# Untitled_-_halv_V3_31.net
KiCad netlist of a schematic drawn in EAGLE
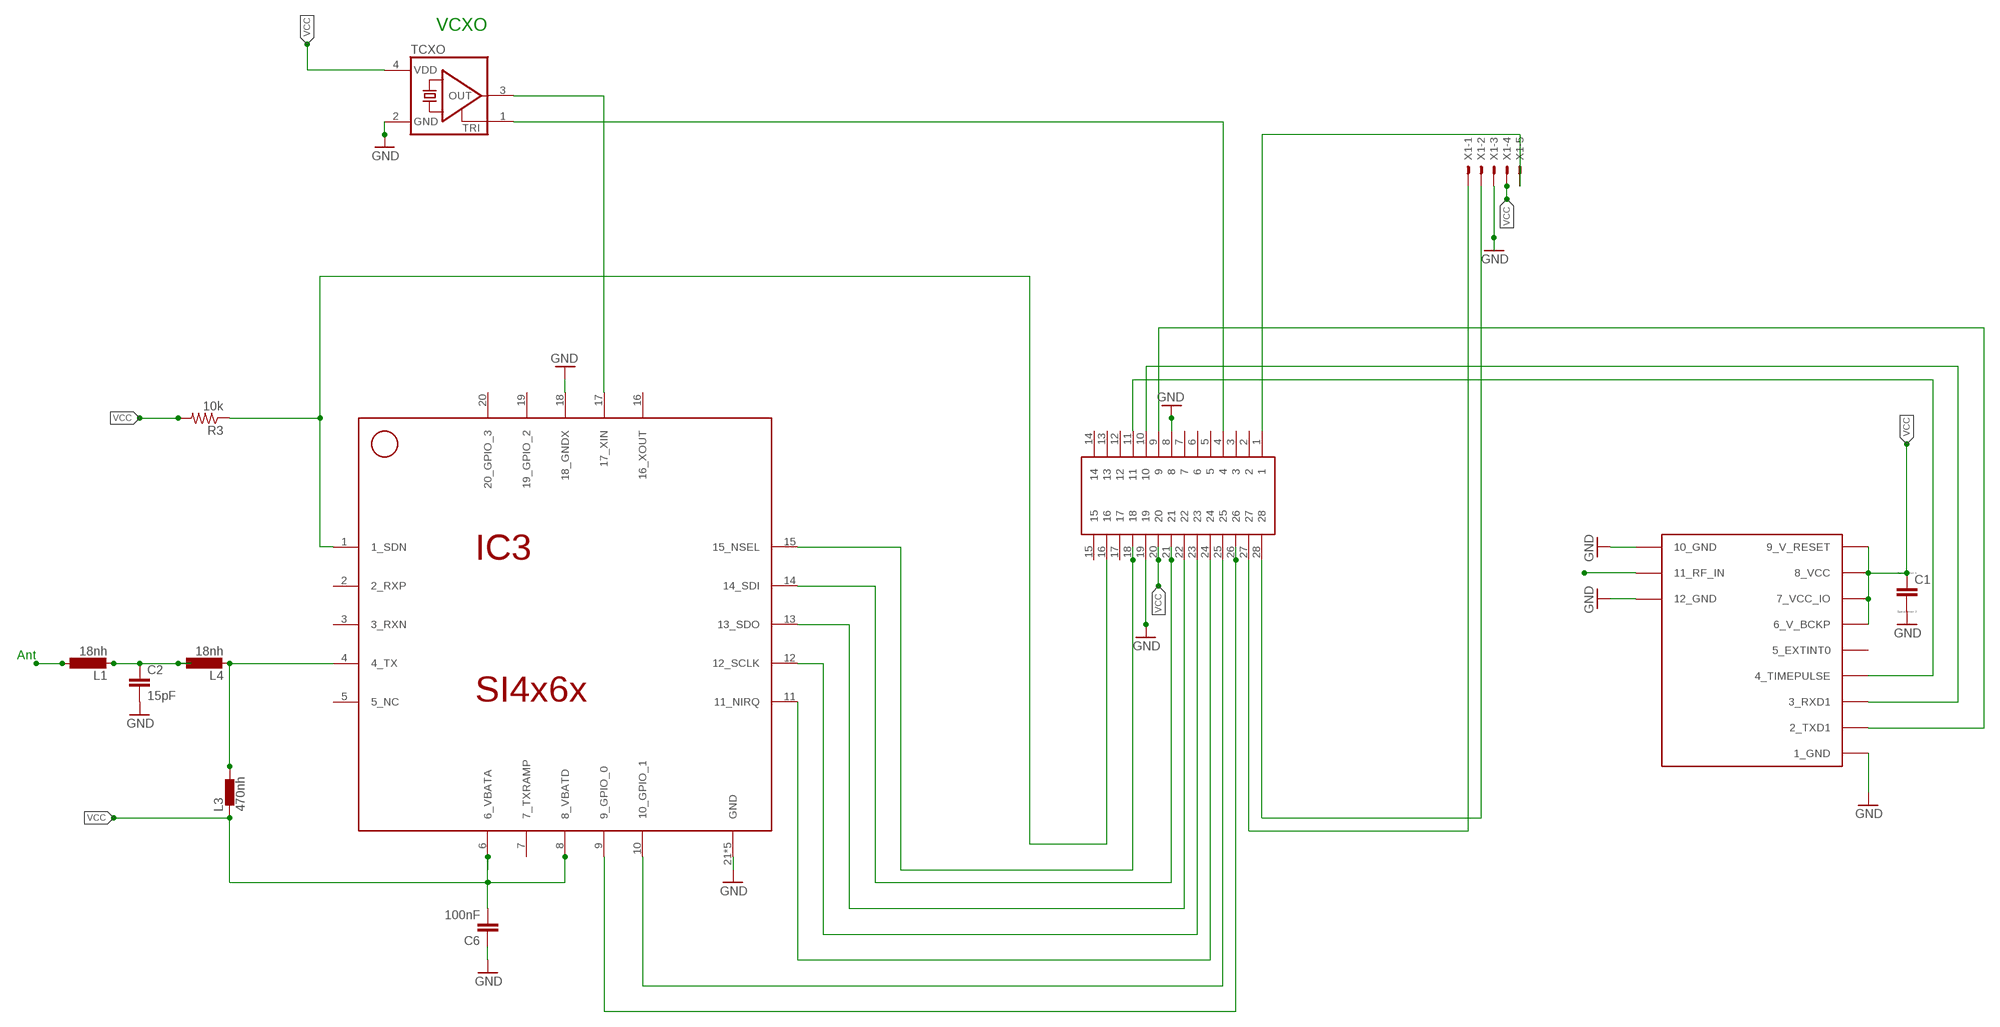
[diagram p0: schematic, sheet 1]

(export (version "E")
  (design (tool "Eeschema 10.0.6"))
  (components
    (comp (ref "C1")
      (value "CC0603")
      (footprint "eagle-import:C0603")
      (libsource (lib "eagle-import") (part "CC0603"))
    )
    (comp (ref "C2")
      (value "15pF")
      (footprint "eagle-import:C0603K")
      (libsource (lib "eagle-import") (part "resistor_348_C-EUC0603K"))
    )
    (comp (ref "C6")
      (value "100nF")
      (footprint "eagle-import:C0402")
      (libsource (lib "eagle-import") (part "C-EUC0402"))
    )
    (comp (ref "IC3")
      (value "SI4x6x")
      (footprint "eagle-import:QFN-20")
      (libsource (lib "eagle-import") (part "SI4463/4"))
    )
    (comp (ref "L1")
      (value "18nh")
      (footprint "eagle-import:L2012C")
      (libsource (lib "eagle-import") (part "L-EUL2012C"))
    )
    (comp (ref "L3")
      (value "470nh")
      (footprint "eagle-import:0402")
      (libsource (lib "eagle-import") (part "BLM15HD601SN1"))
    )
    (comp (ref "L4")
      (value "18nh")
      (footprint "eagle-import:L2012C")
      (libsource (lib "eagle-import") (part "L-EUL2012C"))
    )
    (comp (ref "PIC-VERS3.3")
      (value "SSOP28")
      (footprint "eagle-import:SSOP28DB")
      (libsource (lib "eagle-import") (part "SSOP28"))
    )
    (comp (ref "R3")
      (value "10k")
      (footprint "eagle-import:R0402")
      (libsource (lib "eagle-import") (part "R-US_R0402"))
    )
    (comp (ref "TCXO")
      (value "CRYSTAL_3.2X2.5-TCXO")
      (footprint "eagle-import:CRYSTAL_3.2X2.5-TCXO")
      (libsource (lib "eagle-import") (part "CRYSTAL_3.2X2.5-TCXO"))
    )
    (comp (ref "U$1")
      (value "UBLOX_MAX")
      (footprint "eagle-import:UBLOX_MAX")
      (libsource (lib "eagle-import") (part "UBLOX_MAX"))
    )
    (comp (ref "X1")
      (value "22-23-2051")
      (footprint "eagle-import:22-23-2051")
      (fields (field (name "MF") "MOLEX"))
      (libsource (lib "eagle-import") (part "22-23-2051"))
    )
  )
  (nets
    (net (code "1") (name "GND") (class "Default")
      (node (ref "C1") (pin "2") (pinfunction "2_2") (pintype "passive"))
      (node (ref "C2") (pin "2") (pinfunction "2_2") (pintype "passive"))
      (node (ref "C6") (pin "1") (pinfunction "1_1") (pintype "passive"))
      (node (ref "IC3") (pin "18") (pinfunction "18_GNDX_18") (pintype "bidirectional"))
      (node (ref "IC3") (pin "21") (pinfunction "GND_21") (pintype "bidirectional"))
      (node (ref "IC3") (pin "22") (pinfunction "GND_22") (pintype "bidirectional"))
      (node (ref "IC3") (pin "23") (pinfunction "GND_23") (pintype "bidirectional"))
      (node (ref "IC3") (pin "24") (pinfunction "GND_24") (pintype "bidirectional"))
      (node (ref "IC3") (pin "25") (pinfunction "GND_25") (pintype "bidirectional"))
      (node (ref "PIC-VERS3.3") (pin "19") (pinfunction "19_19") (pintype "bidirectional"))
      (node (ref "PIC-VERS3.3") (pin "8") (pinfunction "8_8") (pintype "bidirectional"))
      (node (ref "TCXO") (pin "2") (pinfunction "GND_2") (pintype "power_in"))
      (node (ref "U$1") (pin "10_GND") (pinfunction "10_GND_10_GND") (pintype "power_in"))
      (node (ref "U$1") (pin "12_GND") (pinfunction "12_GND_12_GND") (pintype "power_in"))
      (node (ref "U$1") (pin "1_GND") (pinfunction "1_GND_1_GND") (pintype "power_in"))
      (node (ref "X1") (pin "3") (pinfunction "S_3") (pintype "passive"))
    )
    (net (code "2") (name "Net-(C2-Pad1)") (class "Default")
      (node (ref "C2") (pin "1") (pinfunction "1_1") (pintype "passive"))
      (node (ref "L1") (pin "2") (pinfunction "2_2") (pintype "passive"))
      (node (ref "L4") (pin "1") (pinfunction "1_1") (pintype "passive"))
    )
    (net (code "3") (name "Net-(IC3-1_SDN)") (class "Default")
      (node (ref "IC3") (pin "1") (pinfunction "1_SDN_1") (pintype "bidirectional"))
      (node (ref "PIC-VERS3.3") (pin "16") (pinfunction "16_16") (pintype "bidirectional"))
      (node (ref "R3") (pin "1") (pinfunction "1_1") (pintype "passive"))
    )
    (net (code "4") (name "Net-(IC3-4_TX)") (class "Default")
      (node (ref "IC3") (pin "4") (pinfunction "4_TX_4") (pintype "bidirectional"))
      (node (ref "L3") (pin "2") (pinfunction "2_2") (pintype "passive"))
      (node (ref "L4") (pin "2") (pinfunction "2_2") (pintype "passive"))
    )
    (net (code "5") (name "Net-(IC3-9_GPIO_0)") (class "Default")
      (node (ref "IC3") (pin "9") (pinfunction "9_GPIO_0_9") (pintype "bidirectional"))
      (node (ref "PIC-VERS3.3") (pin "26") (pinfunction "26_26") (pintype "bidirectional"))
    )
    (net (code "6") (name "Net-(IC3-10_GPIO_1)") (class "Default")
      (node (ref "IC3") (pin "10") (pinfunction "10_GPIO_1_10") (pintype "bidirectional"))
      (node (ref "PIC-VERS3.3") (pin "25") (pinfunction "25_25") (pintype "bidirectional"))
    )
    (net (code "7") (name "Net-(IC3-11_NIRQ)") (class "Default")
      (node (ref "IC3") (pin "11") (pinfunction "11_NIRQ_11") (pintype "bidirectional"))
      (node (ref "PIC-VERS3.3") (pin "24") (pinfunction "24_24") (pintype "bidirectional"))
    )
    (net (code "8") (name "Net-(IC3-12_SCLK)") (class "Default")
      (node (ref "IC3") (pin "12") (pinfunction "12_SCLK_12") (pintype "bidirectional"))
      (node (ref "PIC-VERS3.3") (pin "23") (pinfunction "23_23") (pintype "bidirectional"))
    )
    (net (code "9") (name "Net-(IC3-13_SDO)") (class "Default")
      (node (ref "IC3") (pin "13") (pinfunction "13_SDO_13") (pintype "bidirectional"))
      (node (ref "PIC-VERS3.3") (pin "22") (pinfunction "22_22") (pintype "bidirectional"))
    )
    (net (code "10") (name "Net-(IC3-14_SDI)") (class "Default")
      (node (ref "IC3") (pin "14") (pinfunction "14_SDI_14") (pintype "bidirectional"))
      (node (ref "PIC-VERS3.3") (pin "21") (pinfunction "21_21") (pintype "bidirectional"))
    )
    (net (code "11") (name "Net-(IC3-15_NSEL)") (class "Default")
      (node (ref "IC3") (pin "15") (pinfunction "15_NSEL_15") (pintype "bidirectional"))
      (node (ref "PIC-VERS3.3") (pin "18") (pinfunction "18_18") (pintype "bidirectional"))
    )
    (net (code "12") (name "Net-(IC3-17_XIN)") (class "Default")
      (node (ref "IC3") (pin "17") (pinfunction "17_XIN_17") (pintype "bidirectional"))
      (node (ref "TCXO") (pin "3") (pinfunction "OUT_3") (pintype "output"))
    )
    (net (code "13") (name "Net-(PIC-VERS3.3-Pad9)") (class "Default")
      (node (ref "PIC-VERS3.3") (pin "9") (pinfunction "9_9") (pintype "bidirectional"))
      (node (ref "U$1") (pin "2_TXD1") (pinfunction "2_TXD1_2_TXD1") (pintype "bidirectional"))
    )
    (net (code "14") (name "Net-(PIC-VERS3.3-Pad10)") (class "Default")
      (node (ref "PIC-VERS3.3") (pin "10") (pinfunction "10_10") (pintype "bidirectional"))
      (node (ref "U$1") (pin "3_RXD1") (pinfunction "3_RXD1_3_RXD1") (pintype "bidirectional"))
    )
    (net (code "15") (name "Net-(PIC-VERS3.3-Pad11)") (class "Default")
      (node (ref "PIC-VERS3.3") (pin "11") (pinfunction "11_11") (pintype "bidirectional"))
      (node (ref "U$1") (pin "4_TIMEPULSE") (pinfunction "4_TIMEPULSE_4_TIMEPULSE") (pintype "bidirectional"))
    )
    (net (code "16") (name "Net-(TCXO-TRI)") (class "Default")
      (node (ref "PIC-VERS3.3") (pin "4") (pinfunction "4_4") (pintype "bidirectional"))
      (node (ref "TCXO") (pin "1") (pinfunction "TRI_1") (pintype "input"))
    )
    (net (code "17") (name "Net-(X1A-S)") (class "Default")
      (node (ref "PIC-VERS3.3") (pin "27") (pinfunction "27_27") (pintype "bidirectional"))
      (node (ref "X1") (pin "1") (pinfunction "S_1") (pintype "passive"))
    )
    (net (code "18") (name "Net-(X1B-S)") (class "Default")
      (node (ref "PIC-VERS3.3") (pin "28") (pinfunction "28_28") (pintype "bidirectional"))
      (node (ref "X1") (pin "2") (pinfunction "S_2") (pintype "passive"))
    )
    (net (code "19") (name "Net-(X1E-S)") (class "Default")
      (node (ref "PIC-VERS3.3") (pin "1") (pinfunction "1_1") (pintype "bidirectional"))
      (node (ref "X1") (pin "5") (pinfunction "S_5") (pintype "passive"))
    )
    (net (code "20") (name "VCC") (class "Default")
      (node (ref "C1") (pin "1") (pinfunction "1_1") (pintype "passive"))
      (node (ref "C6") (pin "2") (pinfunction "2_2") (pintype "passive"))
      (node (ref "IC3") (pin "6") (pinfunction "6_VBATA_6") (pintype "bidirectional"))
      (node (ref "IC3") (pin "8") (pinfunction "8_VBATD_8") (pintype "bidirectional"))
      (node (ref "L3") (pin "1") (pinfunction "1_1") (pintype "passive"))
      (node (ref "PIC-VERS3.3") (pin "20") (pinfunction "20_20") (pintype "bidirectional"))
      (node (ref "R3") (pin "2") (pinfunction "2_2") (pintype "passive"))
      (node (ref "TCXO") (pin "4") (pinfunction "VDD_4") (pintype "power_in"))
      (node (ref "U$1") (pin "6_V_BCKP") (pinfunction "6_V_BCKP_6_V_BCKP") (pintype "bidirectional"))
      (node (ref "U$1") (pin "7_VCC_IO") (pinfunction "7_VCC_IO_7_VCC_IO") (pintype "power_in"))
      (node (ref "U$1") (pin "8_VCC") (pinfunction "8_VCC_8_VCC") (pintype "power_in"))
      (node (ref "U$1") (pin "9_V_RESET") (pinfunction "9_V_RESET_9_V_RESET") (pintype "power_in"))
      (node (ref "X1") (pin "4") (pinfunction "S_4") (pintype "passive"))
    )
    (net (code "21") (name "unconnected-(IC3-2_RXP-Pad2)") (class "Default")
      (node (ref "IC3") (pin "2") (pinfunction "2_RXP_2") (pintype "bidirectional"))
    )
    (net (code "22") (name "unconnected-(IC3-3_RXN-Pad3)") (class "Default")
      (node (ref "IC3") (pin "3") (pinfunction "3_RXN_3") (pintype "bidirectional"))
    )
    (net (code "23") (name "unconnected-(IC3-5_NC-Pad5)") (class "Default")
      (node (ref "IC3") (pin "5") (pinfunction "5_NC_5") (pintype "bidirectional"))
    )
    (net (code "24") (name "unconnected-(IC3-7_TXRAMP-Pad7)") (class "Default")
      (node (ref "IC3") (pin "7") (pinfunction "7_TXRAMP_7") (pintype "bidirectional"))
    )
    (net (code "25") (name "unconnected-(IC3-16_XOUT-Pad16)") (class "Default")
      (node (ref "IC3") (pin "16") (pinfunction "16_XOUT_16") (pintype "bidirectional"))
    )
    (net (code "26") (name "unconnected-(IC3-19_GPIO_2-Pad19)") (class "Default")
      (node (ref "IC3") (pin "19") (pinfunction "19_GPIO_2_19") (pintype "bidirectional"))
    )
    (net (code "27") (name "unconnected-(IC3-20_GPIO_3-Pad20)") (class "Default")
      (node (ref "IC3") (pin "20") (pinfunction "20_GPIO_3_20") (pintype "bidirectional"))
    )
    (net (code "28") (name "unconnected-(L1-Pad1)") (class "Default")
      (node (ref "L1") (pin "1") (pinfunction "1_1") (pintype "passive"))
    )
    (net (code "29") (name "unconnected-(PIC-VERS3.3-Pad2)") (class "Default")
      (node (ref "PIC-VERS3.3") (pin "2") (pinfunction "2_2") (pintype "bidirectional"))
    )
    (net (code "30") (name "unconnected-(PIC-VERS3.3-Pad3)") (class "Default")
      (node (ref "PIC-VERS3.3") (pin "3") (pinfunction "3_3") (pintype "bidirectional"))
    )
    (net (code "31") (name "unconnected-(PIC-VERS3.3-Pad5)") (class "Default")
      (node (ref "PIC-VERS3.3") (pin "5") (pinfunction "5_5") (pintype "bidirectional"))
    )
    (net (code "32") (name "unconnected-(PIC-VERS3.3-Pad6)") (class "Default")
      (node (ref "PIC-VERS3.3") (pin "6") (pinfunction "6_6") (pintype "bidirectional"))
    )
    (net (code "33") (name "unconnected-(PIC-VERS3.3-Pad7)") (class "Default")
      (node (ref "PIC-VERS3.3") (pin "7") (pinfunction "7_7") (pintype "bidirectional"))
    )
    (net (code "34") (name "unconnected-(PIC-VERS3.3-Pad12)") (class "Default")
      (node (ref "PIC-VERS3.3") (pin "12") (pinfunction "12_12") (pintype "bidirectional"))
    )
    (net (code "35") (name "unconnected-(PIC-VERS3.3-Pad13)") (class "Default")
      (node (ref "PIC-VERS3.3") (pin "13") (pinfunction "13_13") (pintype "bidirectional"))
    )
    (net (code "36") (name "unconnected-(PIC-VERS3.3-Pad14)") (class "Default")
      (node (ref "PIC-VERS3.3") (pin "14") (pinfunction "14_14") (pintype "bidirectional"))
    )
    (net (code "37") (name "unconnected-(PIC-VERS3.3-Pad15)") (class "Default")
      (node (ref "PIC-VERS3.3") (pin "15") (pinfunction "15_15") (pintype "bidirectional"))
    )
    (net (code "38") (name "unconnected-(PIC-VERS3.3-Pad17)") (class "Default")
      (node (ref "PIC-VERS3.3") (pin "17") (pinfunction "17_17") (pintype "bidirectional"))
    )
    (net (code "39") (name "unconnected-(U$1-Pad5_EXTINT0)") (class "Default")
      (node (ref "U$1") (pin "5_EXTINT0") (pinfunction "5_EXTINT0_5_EXTINT0") (pintype "bidirectional"))
    )
    (net (code "40") (name "unconnected-(U$1-Pad11_RF_IN)") (class "Default")
      (node (ref "U$1") (pin "11_RF_IN") (pinfunction "11_RF_IN_11_RF_IN") (pintype "bidirectional"))
    )
  )
)
